# CH32V303VCT6-R0.net
KiCad netlist of a schematic drawn in Altium Designer
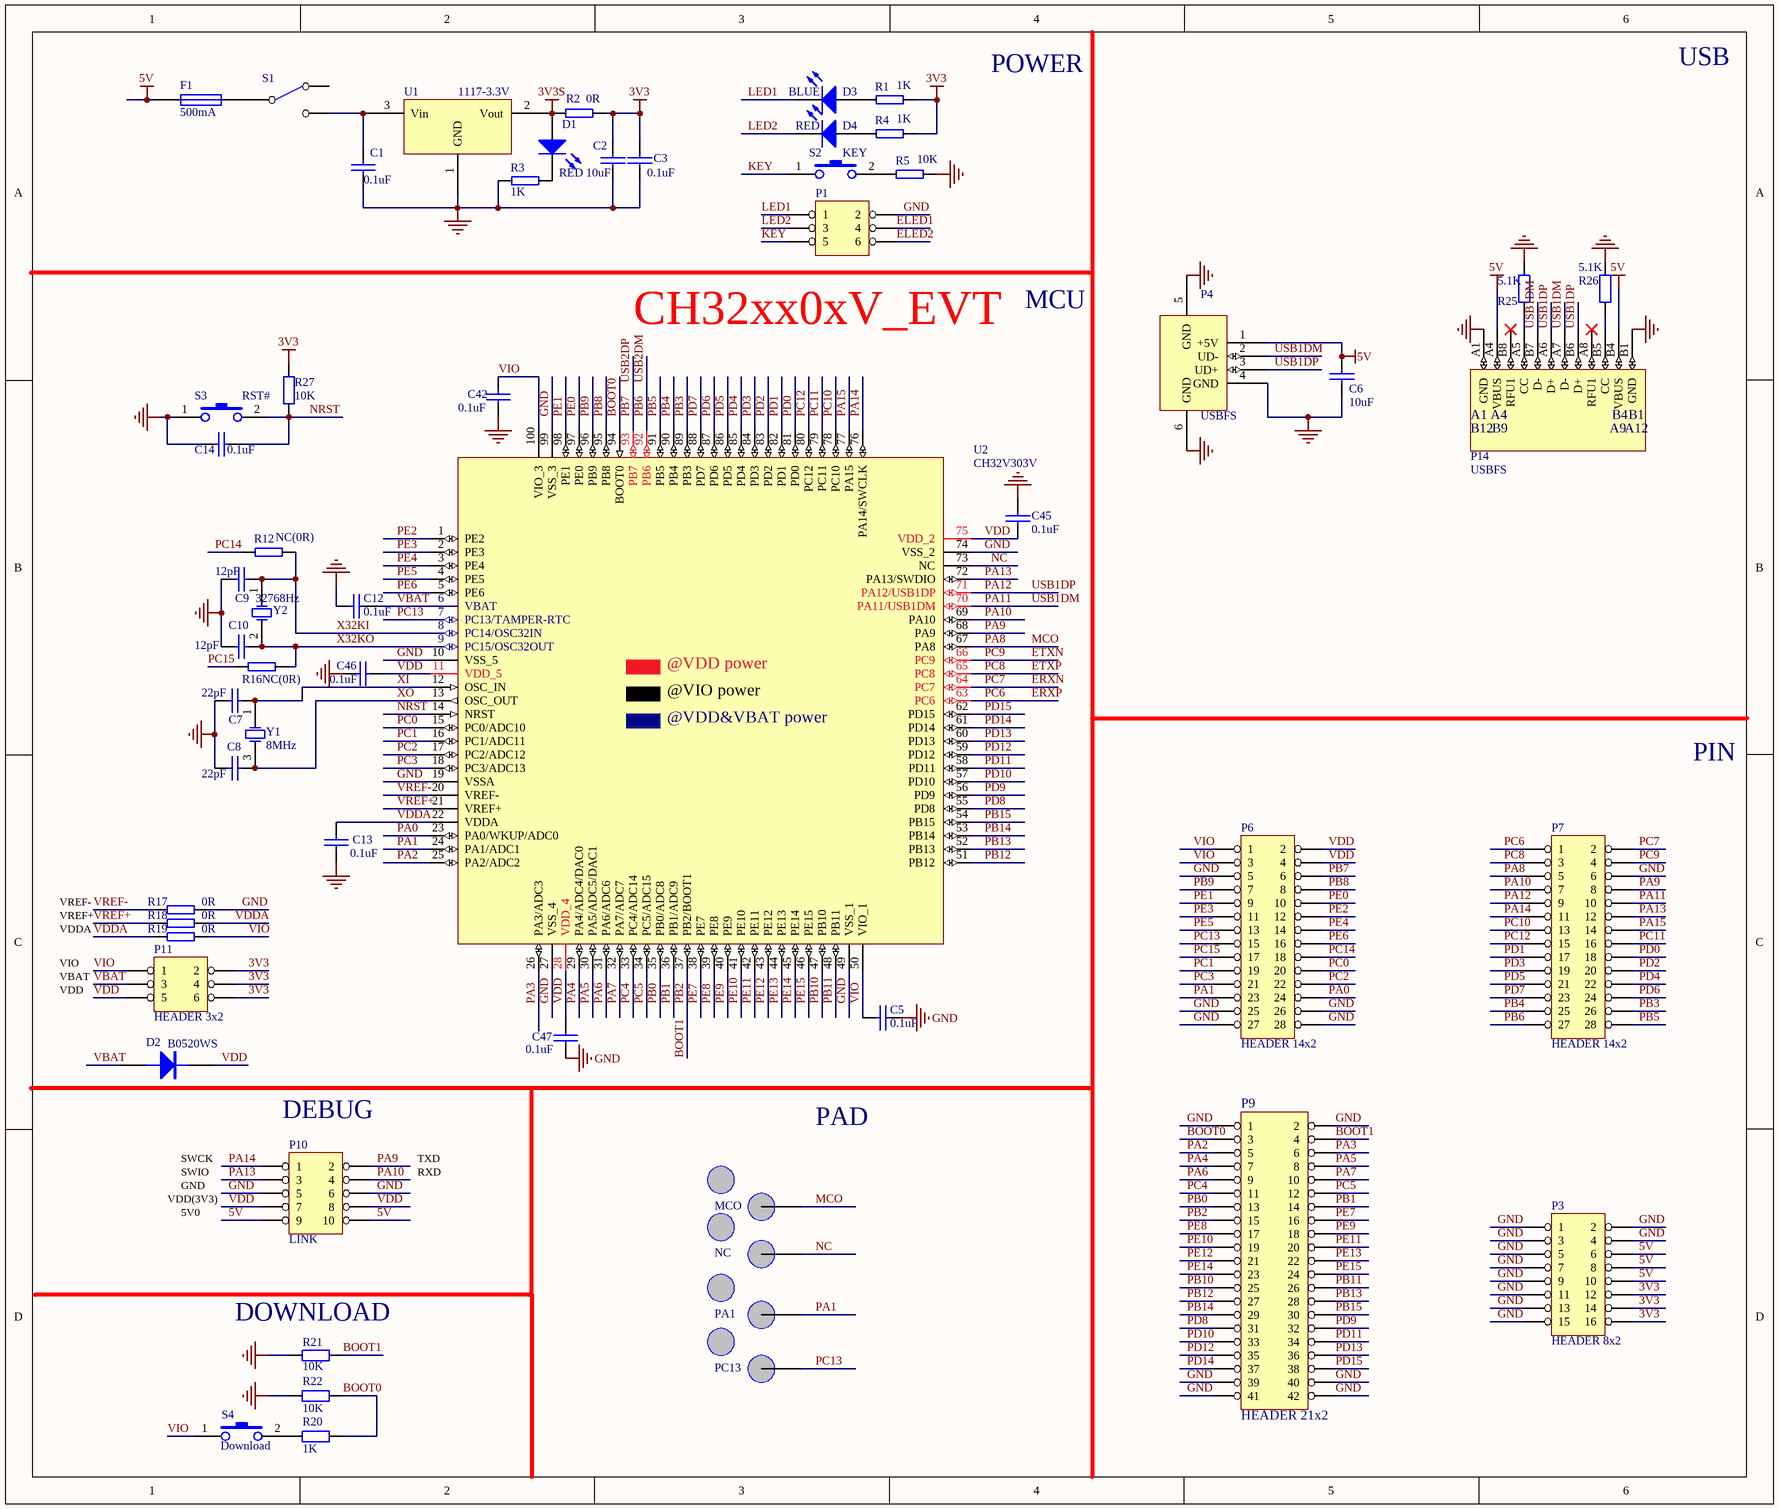
[diagram p0: CH32V303VCT6-R0.SchDoc]

(export (version "E")
  (design (tool "Eeschema 10.0.6"))
  (components
    (comp (ref "C1")
      (value "0.1uF")
      (footprint "0603_C")
      (description "Capacitor")
      (libsource (lib "*") (part "CAP"))
    )
    (comp (ref "C2")
      (value "10uF")
      (footprint "3216_C")
      (description "Capacitor")
      (libsource (lib "*") (part "CAP"))
    )
    (comp (ref "C3")
      (value "0.1uF")
      (footprint "0603_C")
      (description "Capacitor")
      (libsource (lib "*") (part "CAP"))
    )
    (comp (ref "C5")
      (value "0.1uF")
      (footprint "0603_C")
      (description "Capacitor")
      (libsource (lib "*") (part "CAP"))
    )
    (comp (ref "C6")
      (value "10uF")
      (footprint "3216_C")
      (description "Capacitor")
      (libsource (lib "") (part "CAP_1"))
    )
    (comp (ref "C7")
      (value "22pF")
      (footprint "0603_C")
      (description "Capacitor")
      (libsource (lib "*") (part "CAP"))
    )
    (comp (ref "C8")
      (value "22pF")
      (footprint "0603_C")
      (description "Capacitor")
      (libsource (lib "*") (part "CAP"))
    )
    (comp (ref "C9")
      (value "12pF")
      (footprint "0603_C")
      (description "Capacitor")
      (libsource (lib "*") (part "CAP"))
    )
    (comp (ref "C10")
      (value "12pF")
      (footprint "0603_C")
      (description "Capacitor")
      (libsource (lib "*") (part "CAP"))
    )
    (comp (ref "C12")
      (value "0.1uF")
      (footprint "0603_C")
      (description "Capacitor")
      (libsource (lib "*") (part "CAP"))
    )
    (comp (ref "C13")
      (value "0.1uF")
      (footprint "0603_C")
      (description "Capacitor")
      (libsource (lib "*") (part "CAP"))
    )
    (comp (ref "C14")
      (value "0.1uF")
      (footprint "0603_C")
      (description "Capacitor")
      (libsource (lib "") (part "CAP_1"))
    )
    (comp (ref "C42")
      (value "0.1uF")
      (footprint "0603_C")
      (description "Capacitor")
      (libsource (lib "*") (part "CAP"))
    )
    (comp (ref "C45")
      (value "0.1uF")
      (footprint "0603_C")
      (description "Capacitor")
      (libsource (lib "*") (part "CAP"))
    )
    (comp (ref "C46")
      (value "0.1uF")
      (footprint "0603_C")
      (description "Capacitor")
      (libsource (lib "*") (part "CAP"))
    )
    (comp (ref "C47")
      (value "0.1uF")
      (footprint "0603_C")
      (description "Capacitor")
      (libsource (lib "*") (part "CAP"))
    )
    (comp (ref "D1")
      (value "RED")
      (footprint "0603+")
      (description "Typical INFRARED GaAs LED")
      (fields (field (name "PUBLISHER") "Altium Limited"))
      (libsource (lib "*") (part "LED0"))
    )
    (comp (ref "D2")
      (value "B0520WS")
      (footprint "SOD-323")
      (description "Diode")
      (libsource (lib "*") (part "DIODE"))
    )
    (comp (ref "D3")
      (value "BLUE")
      (footprint "0603+")
      (description "Typical INFRARED GaAs LED")
      (fields (field (name "PUBLISHER") "Altium Limited"))
      (libsource (lib "*") (part "LED0"))
    )
    (comp (ref "D4")
      (value "RED")
      (footprint "0603+")
      (description "Typical INFRARED GaAs LED")
      (fields (field (name "PUBLISHER") "Altium Limited"))
      (libsource (lib "*") (part "LED0"))
    )
    (comp (ref "F1")
      (value "500mA")
      (footprint "0805")
      (description "Fuse")
      (libsource (lib "wch_sch_others") (part "FUSE1"))
    )
    (comp (ref "MCO")
      (value "Testpoint")
      (footprint "TESTPOINT1")
      (description "测试点")
      (libsource (lib "wch_sch_others") (part "Testpoint"))
    )
    (comp (ref "NC")
      (value "Testpoint")
      (footprint "TESTPOINT1")
      (description "测试点")
      (libsource (lib "wch_sch_others") (part "Testpoint"))
    )
    (comp (ref "P1")
      (value "IO")
      (footprint "MYPCB:IDC6-2.54mm")
      (description "Header, 3-Pin, Dual row")
      (libsource (lib "wch_sch_others") (part "HEADER 3x2"))
    )
    (comp (ref "P3")
      (value "HEADER 8x2")
      (footprint "MYPCB:IDC16-2.54mm")
      (description "Header, 8-Pin, Dual row")
      (libsource (lib "wch_sch_others") (part "HEADER 8x2"))
    )
    (comp (ref "P4")
      (value "USBFS")
      (footprint "USBAF")
      (description "USB Port")
      (libsource (lib "*") (part "USB"))
    )
    (comp (ref "P6")
      (value "HEADER 14x2")
      (footprint "MYPCB:IDC28-2.54MM")
      (description "Header, 14-Pin, Dual row")
      (libsource (lib "wch_sch_others") (part "HEADER 14x2"))
    )
    (comp (ref "P7")
      (value "HEADER 14x2")
      (footprint "MYPCB:IDC28-2.54MM")
      (description "Header, 14-Pin, Dual row")
      (libsource (lib "wch_sch_others") (part "HEADER 14x2"))
    )
    (comp (ref "P9")
      (value "HEADER 21x2")
      (footprint "MYPCB:IDC42-2.54MM")
      (description "Header, 21-Pin, Dual row")
      (libsource (lib "wch_sch_others") (part "HEADER 21x2"))
    )
    (comp (ref "P10")
      (value "LINK")
      (footprint "MYPCB:IDC10-2.54mm")
      (description "Header, 5-Pin, Dual row")
      (libsource (lib "wch_sch_others") (part "HEADER 5x2"))
    )
    (comp (ref "P11")
      (value "HEADER 3x2")
      (footprint "MYPCB:IDC6-2.54mm")
      (description "Header, 3-Pin, Dual row")
      (libsource (lib "wch_sch_others") (part "HEADER 3x2"))
    )
    (comp (ref "P14")
      (value "USBFS")
      (footprint "TYPE-C-Receptacle-2.0")
      (libsource (lib "*") (part "TYPE-C1"))
    )
    (comp (ref "PA1")
      (value "Testpoint")
      (footprint "TESTPOINT1")
      (description "测试点")
      (libsource (lib "wch_sch_others") (part "Testpoint"))
    )
    (comp (ref "PC13")
      (value "Testpoint")
      (footprint "TESTPOINT1")
      (description "测试点")
      (libsource (lib "wch_sch_others") (part "Testpoint"))
    )
    (comp (ref "R1") (value "1K") (footprint "0603") (libsource (lib "wch_sch_others") (part "RES")))
    (comp (ref "R2") (value "0R") (footprint "0603") (libsource (lib "wch_sch_others") (part "RES")))
    (comp (ref "R3") (value "1K") (footprint "0603") (libsource (lib "wch_sch_others") (part "RES")))
    (comp (ref "R4") (value "1K") (footprint "0603") (libsource (lib "wch_sch_others") (part "RES")))
    (comp (ref "R5") (value "10K") (footprint "0603") (libsource (lib "wch_sch_others") (part "RES")))
    (comp (ref "R12") (value "NC(0R)") (footprint "0603") (libsource (lib "wch_sch_others") (part "RES")))
    (comp (ref "R16") (value "NC(0R)") (footprint "0603") (libsource (lib "wch_sch_others") (part "RES")))
    (comp (ref "R17") (value "0R") (footprint "0603") (libsource (lib "*") (part "R")))
    (comp (ref "R18") (value "0R") (footprint "0603") (libsource (lib "*") (part "R")))
    (comp (ref "R19") (value "0R") (footprint "0603") (libsource (lib "*") (part "R")))
    (comp (ref "R20")
      (value "1K")
      (footprint "0603")
      (description "Resistor")
      (fields (field (name "PUBLISHER") "Altium Limited"))
      (libsource (lib "Miscellaneous Devices") (part "Res2"))
    )
    (comp (ref "R21")
      (value "10K")
      (footprint "0603")
      (description "Resistor")
      (fields (field (name "PUBLISHER") "Altium Limited"))
      (libsource (lib "Miscellaneous Devices") (part "Res2"))
    )
    (comp (ref "R22")
      (value "10K")
      (footprint "0603")
      (description "Resistor")
      (fields (field (name "PUBLISHER") "Altium Limited"))
      (libsource (lib "Miscellaneous Devices") (part "Res2"))
    )
    (comp (ref "R25")
      (value "5.1K")
      (footprint "0603")
      (description "Resistor")
      (libsource (lib "") (part "Res2_1"))
    )
    (comp (ref "R26")
      (value "5.1K")
      (footprint "0603")
      (description "Resistor")
      (libsource (lib "") (part "Res2_1"))
    )
    (comp (ref "R27")
      (value "10K")
      (footprint "0603")
      (description "Resistor")
      (fields (field (name "PUBLISHER") "Altium Limited"))
      (libsource (lib "") (part "Res2_1"))
    )
    (comp (ref "S1") (value "SW SPDT") (footprint "KEY2") (libsource (lib "*") (part "SW SPDT")))
    (comp (ref "S2")
      (value "KEY")
      (footprint "SMD_6.1x3.65x2.5mm-KEY")
      (libsource (lib "wch_sch_others") (part "KEY1"))
    )
    (comp (ref "S3")
      (value "RST#")
      (footprint "SMD_6.1x3.65x2.5mm-KEY")
      (libsource (lib "wch_sch_others") (part "KEY1"))
    )
    (comp (ref "S4")
      (value "Download")
      (footprint "SMD_6.1x3.65x2.5mm-KEY")
      (libsource (lib "wch_sch_others") (part "KEY1"))
    )
    (comp (ref "U1")
      (value "1117-3.3V")
      (footprint "SOT-223")
      (libsource (lib "wch_sch_others") (part "1117-3.3V"))
    )
    (comp (ref "U2")
      (value "CH32V303V")
      (footprint "LQFP100")
      (description "RISC-V FPU HD-MCU, 144MHz, 8*UART, 10*Timer, 4*OPA")
      (libsource (lib "CHXXX") (part "CH32V303V"))
    )
    (comp (ref "Y1")
      (value "8MHz")
      (footprint "XT3225")
      (description "Crystal Oscillator")
      (fields (field (name "PUBLISHER") "Altium Limited"))
      (libsource (lib "*") (part "XTAL"))
    )
    (comp (ref "Y2")
      (value "32768Hz")
      (footprint "FC-135")
      (description "Crystal Oscillator")
      (fields (field (name "PUBLISHER") "Altium Limited"))
      (libsource (lib "") (part "XTAL_1"))
    )
  )
  (nets
    (net (code "2") (name "/BOOT0") (class "Default")
      (node (ref "P9") (pin "3") (pinfunction "3_3") (pintype "passive"))
      (node (ref "R20") (pin "1") (pinfunction "1_1") (pintype "passive"))
      (node (ref "R22") (pin "1") (pinfunction "1_1") (pintype "passive"))
      (node (ref "U2") (pin "94") (pinfunction "BOOT0_94") (pintype "input"))
    )
    (net (code "3") (name "/BOOT1") (class "Default")
      (node (ref "P9") (pin "15") (pinfunction "15_15") (pintype "passive"))
      (node (ref "P9") (pin "4") (pinfunction "4_4") (pintype "passive"))
      (node (ref "R21") (pin "1") (pinfunction "1_1") (pintype "passive"))
      (node (ref "U2") (pin "37") (pinfunction "PB2/BOOT1_37") (pintype "bidirectional"))
    )
    (net (code "4") (name "/ELED1") (class "Default")
      (node (ref "P1") (pin "4") (pinfunction "4_4") (pintype "passive"))
    )
    (net (code "5") (name "/ELED2") (class "Default")
      (node (ref "P1") (pin "6") (pinfunction "6_6") (pintype "passive"))
    )
    (net (code "6") (name "/ERXN") (class "Default")
      (node (ref "P7") (pin "2") (pinfunction "2_2") (pintype "passive"))
      (node (ref "U2") (pin "64") (pinfunction "PC7_64") (pintype "bidirectional"))
    )
    (net (code "7") (name "/ERXP") (class "Default")
      (node (ref "P7") (pin "1") (pinfunction "1_1") (pintype "passive"))
      (node (ref "U2") (pin "63") (pinfunction "PC6_63") (pintype "bidirectional"))
    )
    (net (code "8") (name "/ETXN") (class "Default")
      (node (ref "P7") (pin "4") (pinfunction "4_4") (pintype "passive"))
      (node (ref "U2") (pin "66") (pinfunction "PC9_66") (pintype "bidirectional"))
    )
    (net (code "9") (name "/ETXP") (class "Default")
      (node (ref "P7") (pin "3") (pinfunction "3_3") (pintype "passive"))
      (node (ref "U2") (pin "65") (pinfunction "PC8_65") (pintype "bidirectional"))
    )
    (net (code "10") (name "/KEY") (class "Default")
      (node (ref "P1") (pin "5") (pinfunction "5_5") (pintype "passive"))
      (node (ref "S2") (pin "1") (pinfunction "1_1") (pintype "passive"))
    )
    (net (code "11") (name "/LED1") (class "Default")
      (node (ref "D3") (pin "2") (pinfunction "K_2") (pintype "passive"))
      (node (ref "P1") (pin "1") (pinfunction "1_1") (pintype "passive"))
    )
    (net (code "12") (name "/LED2") (class "Default")
      (node (ref "D4") (pin "2") (pinfunction "K_2") (pintype "passive"))
      (node (ref "P1") (pin "3") (pinfunction "3_3") (pintype "passive"))
    )
    (net (code "13") (name "/MCO") (class "Default")
      (node (ref "MCO") (pin "1") (pinfunction "point_1") (pintype "passive"))
      (node (ref "P7") (pin "5") (pinfunction "5_5") (pintype "passive"))
      (node (ref "U2") (pin "67") (pinfunction "PA8_67") (pintype "bidirectional"))
    )
    (net (code "14") (name "/NC") (class "Default")
      (node (ref "NC") (pin "1") (pinfunction "point_1") (pintype "passive"))
      (node (ref "U2") (pin "73") (pinfunction "NC_73") (pintype "tri_state"))
    )
    (net (code "15") (name "/NRST") (class "Default")
      (node (ref "C14") (pin "2") (pinfunction "2_2") (pintype "passive"))
      (node (ref "R27") (pin "1") (pinfunction "1_1") (pintype "passive"))
      (node (ref "S3") (pin "2") (pinfunction "2_2") (pintype "passive"))
      (node (ref "U2") (pin "14") (pinfunction "NRST_14") (pintype "input"))
    )
    (net (code "16") (name "/PA0") (class "Default")
      (node (ref "P6") (pin "24") (pinfunction "24_24") (pintype "passive"))
      (node (ref "U2") (pin "23") (pinfunction "PA0/WKUP/ADC0_23") (pintype "bidirectional"))
    )
    (net (code "17") (name "/PA1") (class "Default")
      (node (ref "P6") (pin "23") (pinfunction "23_23") (pintype "passive"))
      (node (ref "PA1") (pin "1") (pinfunction "point_1") (pintype "passive"))
      (node (ref "U2") (pin "24") (pinfunction "PA1/ADC1_24") (pintype "bidirectional"))
    )
    (net (code "18") (name "/PA2") (class "Default")
      (node (ref "P9") (pin "5") (pinfunction "5_5") (pintype "passive"))
      (node (ref "U2") (pin "25") (pinfunction "PA2/ADC2_25") (pintype "bidirectional"))
    )
    (net (code "19") (name "/PA3") (class "Default")
      (node (ref "P9") (pin "6") (pinfunction "6_6") (pintype "passive"))
      (node (ref "U2") (pin "26") (pinfunction "PA3/ADC3_26") (pintype "bidirectional"))
    )
    (net (code "20") (name "/PA4") (class "Default")
      (node (ref "P9") (pin "7") (pinfunction "7_7") (pintype "passive"))
      (node (ref "U2") (pin "29") (pinfunction "PA4/ADC4/DAC0_29") (pintype "bidirectional"))
    )
    (net (code "21") (name "/PA5") (class "Default")
      (node (ref "P9") (pin "8") (pinfunction "8_8") (pintype "passive"))
      (node (ref "U2") (pin "30") (pinfunction "PA5/ADC5/DAC1_30") (pintype "bidirectional"))
    )
    (net (code "22") (name "/PA6") (class "Default")
      (node (ref "P9") (pin "9") (pinfunction "9_9") (pintype "passive"))
      (node (ref "U2") (pin "31") (pinfunction "PA6/ADC6_31") (pintype "bidirectional"))
    )
    (net (code "23") (name "/PA7") (class "Default")
      (node (ref "P9") (pin "10") (pinfunction "10_10") (pintype "passive"))
      (node (ref "U2") (pin "32") (pinfunction "PA7/ADC7_32") (pintype "bidirectional"))
    )
    (net (code "24") (name "/PA9") (class "Default")
      (node (ref "P10") (pin "2") (pinfunction "2_2") (pintype "passive"))
      (node (ref "P7") (pin "8") (pinfunction "8_8") (pintype "passive"))
      (node (ref "U2") (pin "68") (pinfunction "PA9_68") (pintype "bidirectional"))
    )
    (net (code "25") (name "/PA10") (class "Default")
      (node (ref "P10") (pin "4") (pinfunction "4_4") (pintype "passive"))
      (node (ref "P7") (pin "7") (pinfunction "7_7") (pintype "passive"))
      (node (ref "U2") (pin "69") (pinfunction "PA10_69") (pintype "bidirectional"))
    )
    (net (code "26") (name "/PA11") (class "Default")
      (node (ref "P14") (pin "A7") (pinfunction "D-_A7") (pintype "bidirectional"))
      (node (ref "P14") (pin "B7") (pinfunction "D-_B7") (pintype "bidirectional"))
      (node (ref "P4") (pin "2") (pinfunction "UD-_2") (pintype "bidirectional"))
      (node (ref "P7") (pin "10") (pinfunction "10_10") (pintype "passive"))
      (node (ref "U2") (pin "70") (pinfunction "PA11/USB1DM_70") (pintype "bidirectional"))
    )
    (net (code "27") (name "/PA12") (class "Default")
      (node (ref "P14") (pin "A6") (pinfunction "D+_A6") (pintype "bidirectional"))
      (node (ref "P14") (pin "B6") (pinfunction "D+_B6") (pintype "bidirectional"))
      (node (ref "P4") (pin "3") (pinfunction "UD+_3") (pintype "bidirectional"))
      (node (ref "P7") (pin "9") (pinfunction "9_9") (pintype "passive"))
      (node (ref "U2") (pin "71") (pinfunction "PA12/USB1DP_71") (pintype "bidirectional"))
    )
    (net (code "28") (name "/PA13") (class "Default")
      (node (ref "P10") (pin "3") (pinfunction "3_3") (pintype "passive"))
      (node (ref "P7") (pin "12") (pinfunction "12_12") (pintype "passive"))
      (node (ref "U2") (pin "72") (pinfunction "PA13/SWDIO_72") (pintype "bidirectional"))
    )
    (net (code "29") (name "/PA14") (class "Default")
      (node (ref "P10") (pin "1") (pinfunction "1_1") (pintype "passive"))
      (node (ref "P7") (pin "11") (pinfunction "11_11") (pintype "passive"))
      (node (ref "U2") (pin "76") (pinfunction "PA14/SWCLK_76") (pintype "bidirectional"))
    )
    (net (code "30") (name "/PA15") (class "Default")
      (node (ref "P7") (pin "14") (pinfunction "14_14") (pintype "passive"))
      (node (ref "U2") (pin "77") (pinfunction "PA15_77") (pintype "bidirectional"))
    )
    (net (code "31") (name "/PB0") (class "Default")
      (node (ref "P9") (pin "13") (pinfunction "13_13") (pintype "passive"))
      (node (ref "U2") (pin "35") (pinfunction "PB0/ADC8_35") (pintype "bidirectional"))
    )
    (net (code "32") (name "/PB1") (class "Default")
      (node (ref "P9") (pin "14") (pinfunction "14_14") (pintype "passive"))
      (node (ref "U2") (pin "36") (pinfunction "PB1/ADC9_36") (pintype "bidirectional"))
    )
    (net (code "33") (name "/PB3") (class "Default")
      (node (ref "P7") (pin "26") (pinfunction "26_26") (pintype "passive"))
      (node (ref "U2") (pin "89") (pinfunction "PB3_89") (pintype "bidirectional"))
    )
    (net (code "34") (name "/PB4") (class "Default")
      (node (ref "P7") (pin "25") (pinfunction "25_25") (pintype "passive"))
      (node (ref "U2") (pin "90") (pinfunction "PB4_90") (pintype "bidirectional"))
    )
    (net (code "35") (name "/PB5") (class "Default")
      (node (ref "P7") (pin "28") (pinfunction "28_28") (pintype "passive"))
      (node (ref "U2") (pin "91") (pinfunction "PB5_91") (pintype "bidirectional"))
    )
    (net (code "36") (name "/PB6") (class "Default")
      (node (ref "P7") (pin "27") (pinfunction "27_27") (pintype "passive"))
      (node (ref "U2") (pin "92") (pinfunction "PB6_92") (pintype "bidirectional"))
    )
    (net (code "37") (name "/PB7") (class "Default")
      (node (ref "P6") (pin "6") (pinfunction "6_6") (pintype "passive"))
      (node (ref "U2") (pin "93") (pinfunction "PB7_93") (pintype "bidirectional"))
    )
    (net (code "38") (name "/PB8") (class "Default")
      (node (ref "P6") (pin "8") (pinfunction "8_8") (pintype "passive"))
      (node (ref "U2") (pin "95") (pinfunction "PB8_95") (pintype "bidirectional"))
    )
    (net (code "39") (name "/PB9") (class "Default")
      (node (ref "P6") (pin "7") (pinfunction "7_7") (pintype "passive"))
      (node (ref "U2") (pin "96") (pinfunction "PB9_96") (pintype "bidirectional"))
    )
    (net (code "40") (name "/PB10") (class "Default")
      (node (ref "P9") (pin "25") (pinfunction "25_25") (pintype "passive"))
      (node (ref "U2") (pin "47") (pinfunction "PB10_47") (pintype "bidirectional"))
    )
    (net (code "41") (name "/PB11") (class "Default")
      (node (ref "P9") (pin "26") (pinfunction "26_26") (pintype "passive"))
      (node (ref "U2") (pin "48") (pinfunction "PB11_48") (pintype "bidirectional"))
    )
    (net (code "42") (name "/PB12") (class "Default")
      (node (ref "P9") (pin "27") (pinfunction "27_27") (pintype "passive"))
      (node (ref "U2") (pin "51") (pinfunction "PB12_51") (pintype "bidirectional"))
    )
    (net (code "43") (name "/PB13") (class "Default")
      (node (ref "P9") (pin "28") (pinfunction "28_28") (pintype "passive"))
      (node (ref "U2") (pin "52") (pinfunction "PB13_52") (pintype "bidirectional"))
    )
    (net (code "44") (name "/PB14") (class "Default")
      (node (ref "P9") (pin "29") (pinfunction "29_29") (pintype "passive"))
      (node (ref "U2") (pin "53") (pinfunction "PB14_53") (pintype "bidirectional"))
    )
    (net (code "45") (name "/PB15") (class "Default")
      (node (ref "P9") (pin "30") (pinfunction "30_30") (pintype "passive"))
      (node (ref "U2") (pin "54") (pinfunction "PB15_54") (pintype "bidirectional"))
    )
    (net (code "46") (name "/PC0") (class "Default")
      (node (ref "P6") (pin "20") (pinfunction "20_20") (pintype "passive"))
      (node (ref "U2") (pin "15") (pinfunction "PC0/ADC10_15") (pintype "bidirectional"))
    )
    (net (code "47") (name "/PC1") (class "Default")
      (node (ref "P6") (pin "19") (pinfunction "19_19") (pintype "passive"))
      (node (ref "U2") (pin "16") (pinfunction "PC1/ADC11_16") (pintype "bidirectional"))
    )
    (net (code "48") (name "/PC2") (class "Default")
      (node (ref "P6") (pin "22") (pinfunction "22_22") (pintype "passive"))
      (node (ref "U2") (pin "17") (pinfunction "PC2/ADC12_17") (pintype "bidirectional"))
    )
    (net (code "49") (name "/PC3") (class "Default")
      (node (ref "P6") (pin "21") (pinfunction "21_21") (pintype "passive"))
      (node (ref "U2") (pin "18") (pinfunction "PC3/ADC13_18") (pintype "bidirectional"))
    )
    (net (code "50") (name "/PC4") (class "Default")
      (node (ref "P9") (pin "11") (pinfunction "11_11") (pintype "passive"))
      (node (ref "U2") (pin "33") (pinfunction "PC4/ADC14_33") (pintype "bidirectional"))
    )
    (net (code "51") (name "/PC5") (class "Default")
      (node (ref "P9") (pin "12") (pinfunction "12_12") (pintype "passive"))
      (node (ref "U2") (pin "34") (pinfunction "PC5/ADC15_34") (pintype "bidirectional"))
    )
    (net (code "52") (name "/PC10") (class "Default")
      (node (ref "P7") (pin "13") (pinfunction "13_13") (pintype "passive"))
      (node (ref "U2") (pin "78") (pinfunction "PC10_78") (pintype "bidirectional"))
    )
    (net (code "53") (name "/PC11") (class "Default")
      (node (ref "P7") (pin "16") (pinfunction "16_16") (pintype "passive"))
      (node (ref "U2") (pin "79") (pinfunction "PC11_79") (pintype "bidirectional"))
    )
    (net (code "54") (name "/PC12") (class "Default")
      (node (ref "P7") (pin "15") (pinfunction "15_15") (pintype "passive"))
      (node (ref "U2") (pin "80") (pinfunction "PC12_80") (pintype "bidirectional"))
    )
    (net (code "55") (name "/PC13") (class "Default")
      (node (ref "P6") (pin "15") (pinfunction "15_15") (pintype "passive"))
      (node (ref "PC13") (pin "1") (pinfunction "point_1") (pintype "passive"))
      (node (ref "U2") (pin "7") (pinfunction "PC13/TAMPER-RTC_7") (pintype "bidirectional"))
    )
    (net (code "56") (name "/PC14") (class "Default")
      (node (ref "P6") (pin "18") (pinfunction "18_18") (pintype "passive"))
      (node (ref "R12") (pin "1") (pintype "passive"))
    )
    (net (code "57") (name "/PC15") (class "Default")
      (node (ref "P6") (pin "17") (pinfunction "17_17") (pintype "passive"))
      (node (ref "R16") (pin "1") (pintype "passive"))
    )
    (net (code "58") (name "/PD0") (class "Default")
      (node (ref "P7") (pin "18") (pinfunction "18_18") (pintype "passive"))
      (node (ref "U2") (pin "81") (pinfunction "PD0_81") (pintype "bidirectional"))
    )
    (net (code "59") (name "/PD1") (class "Default")
      (node (ref "P7") (pin "17") (pinfunction "17_17") (pintype "passive"))
      (node (ref "U2") (pin "82") (pinfunction "PD1_82") (pintype "bidirectional"))
    )
    (net (code "60") (name "/PD2") (class "Default")
      (node (ref "P7") (pin "20") (pinfunction "20_20") (pintype "passive"))
      (node (ref "U2") (pin "83") (pinfunction "PD2_83") (pintype "bidirectional"))
    )
    (net (code "61") (name "/PD3") (class "Default")
      (node (ref "P7") (pin "19") (pinfunction "19_19") (pintype "passive"))
      (node (ref "U2") (pin "84") (pinfunction "PD3_84") (pintype "bidirectional"))
    )
    (net (code "62") (name "/PD4") (class "Default")
      (node (ref "P7") (pin "22") (pinfunction "22_22") (pintype "passive"))
      (node (ref "U2") (pin "85") (pinfunction "PD4_85") (pintype "bidirectional"))
    )
    (net (code "63") (name "/PD5") (class "Default")
      (node (ref "P7") (pin "21") (pinfunction "21_21") (pintype "passive"))
      (node (ref "U2") (pin "86") (pinfunction "PD5_86") (pintype "bidirectional"))
    )
    (net (code "64") (name "/PD6") (class "Default")
      (node (ref "P7") (pin "24") (pinfunction "24_24") (pintype "passive"))
      (node (ref "U2") (pin "87") (pinfunction "PD6_87") (pintype "bidirectional"))
    )
    (net (code "65") (name "/PD7") (class "Default")
      (node (ref "P7") (pin "23") (pinfunction "23_23") (pintype "passive"))
      (node (ref "U2") (pin "88") (pinfunction "PD7_88") (pintype "bidirectional"))
    )
    (net (code "66") (name "/PD8") (class "Default")
      (node (ref "P9") (pin "31") (pinfunction "31_31") (pintype "passive"))
      (node (ref "U2") (pin "55") (pinfunction "PD8_55") (pintype "bidirectional"))
    )
    (net (code "67") (name "/PD9") (class "Default")
      (node (ref "P9") (pin "32") (pinfunction "32_32") (pintype "passive"))
      (node (ref "U2") (pin "56") (pinfunction "PD9_56") (pintype "bidirectional"))
    )
    (net (code "68") (name "/PD10") (class "Default")
      (node (ref "P9") (pin "33") (pinfunction "33_33") (pintype "passive"))
      (node (ref "U2") (pin "57") (pinfunction "PD10_57") (pintype "bidirectional"))
    )
    (net (code "69") (name "/PD11") (class "Default")
      (node (ref "P9") (pin "34") (pinfunction "34_34") (pintype "passive"))
      (node (ref "U2") (pin "58") (pinfunction "PD11_58") (pintype "bidirectional"))
    )
    (net (code "70") (name "/PD12") (class "Default")
      (node (ref "P9") (pin "35") (pinfunction "35_35") (pintype "passive"))
      (node (ref "U2") (pin "59") (pinfunction "PD12_59") (pintype "bidirectional"))
    )
    (net (code "71") (name "/PD13") (class "Default")
      (node (ref "P9") (pin "36") (pinfunction "36_36") (pintype "passive"))
      (node (ref "U2") (pin "60") (pinfunction "PD13_60") (pintype "bidirectional"))
    )
    (net (code "72") (name "/PD14") (class "Default")
      (node (ref "P9") (pin "37") (pinfunction "37_37") (pintype "passive"))
      (node (ref "U2") (pin "61") (pinfunction "PD14_61") (pintype "bidirectional"))
    )
    (net (code "73") (name "/PD15") (class "Default")
      (node (ref "P9") (pin "38") (pinfunction "38_38") (pintype "passive"))
      (node (ref "U2") (pin "62") (pinfunction "PD15_62") (pintype "bidirectional"))
    )
    (net (code "74") (name "/PE0") (class "Default")
      (node (ref "P6") (pin "10") (pinfunction "10_10") (pintype "passive"))
      (node (ref "U2") (pin "97") (pinfunction "PE0_97") (pintype "bidirectional"))
    )
    (net (code "75") (name "/PE1") (class "Default")
      (node (ref "P6") (pin "9") (pinfunction "9_9") (pintype "passive"))
      (node (ref "U2") (pin "98") (pinfunction "PE1_98") (pintype "bidirectional"))
    )
    (net (code "76") (name "/PE2") (class "Default")
      (node (ref "P6") (pin "12") (pinfunction "12_12") (pintype "passive"))
      (node (ref "U2") (pin "1") (pinfunction "PE2_1") (pintype "bidirectional"))
    )
    (net (code "77") (name "/PE3") (class "Default")
      (node (ref "P6") (pin "11") (pinfunction "11_11") (pintype "passive"))
      (node (ref "U2") (pin "2") (pinfunction "PE3_2") (pintype "bidirectional"))
    )
    (net (code "78") (name "/PE4") (class "Default")
      (node (ref "P6") (pin "14") (pinfunction "14_14") (pintype "passive"))
      (node (ref "U2") (pin "3") (pinfunction "PE4_3") (pintype "bidirectional"))
    )
    (net (code "79") (name "/PE5") (class "Default")
      (node (ref "P6") (pin "13") (pinfunction "13_13") (pintype "passive"))
      (node (ref "U2") (pin "4") (pinfunction "PE5_4") (pintype "bidirectional"))
    )
    (net (code "80") (name "/PE6") (class "Default")
      (node (ref "P6") (pin "16") (pinfunction "16_16") (pintype "passive"))
      (node (ref "U2") (pin "5") (pinfunction "PE6_5") (pintype "bidirectional"))
    )
    (net (code "81") (name "/PE7") (class "Default")
      (node (ref "P9") (pin "16") (pinfunction "16_16") (pintype "passive"))
      (node (ref "U2") (pin "38") (pinfunction "PE7_38") (pintype "bidirectional"))
    )
    (net (code "82") (name "/PE8") (class "Default")
      (node (ref "P9") (pin "17") (pinfunction "17_17") (pintype "passive"))
      (node (ref "U2") (pin "39") (pinfunction "PE8_39") (pintype "bidirectional"))
    )
    (net (code "83") (name "/PE9") (class "Default")
      (node (ref "P9") (pin "18") (pinfunction "18_18") (pintype "passive"))
      (node (ref "U2") (pin "40") (pinfunction "PE9_40") (pintype "bidirectional"))
    )
    (net (code "84") (name "/PE10") (class "Default")
      (node (ref "P9") (pin "19") (pinfunction "19_19") (pintype "passive"))
      (node (ref "U2") (pin "41") (pinfunction "PE10_41") (pintype "bidirectional"))
    )
    (net (code "85") (name "/PE11") (class "Default")
      (node (ref "P9") (pin "20") (pinfunction "20_20") (pintype "passive"))
      (node (ref "U2") (pin "42") (pinfunction "PE11_42") (pintype "bidirectional"))
    )
    (net (code "86") (name "/PE12") (class "Default")
      (node (ref "P9") (pin "21") (pinfunction "21_21") (pintype "passive"))
      (node (ref "U2") (pin "43") (pinfunction "PE12_43") (pintype "bidirectional"))
    )
    (net (code "87") (name "/PE13") (class "Default")
      (node (ref "P9") (pin "22") (pinfunction "22_22") (pintype "passive"))
      (node (ref "U2") (pin "44") (pinfunction "PE13_44") (pintype "bidirectional"))
    )
    (net (code "88") (name "/PE14") (class "Default")
      (node (ref "P9") (pin "23") (pinfunction "23_23") (pintype "passive"))
      (node (ref "U2") (pin "45") (pinfunction "PE14_45") (pintype "bidirectional"))
    )
    (net (code "89") (name "/PE15") (class "Default")
      (node (ref "P9") (pin "24") (pinfunction "24_24") (pintype "passive"))
      (node (ref "U2") (pin "46") (pinfunction "PE15_46") (pintype "bidirectional"))
    )
    (net (code "90") (name "/VBAT") (class "Default")
      (node (ref "C12") (pin "2") (pinfunction "2_2") (pintype "passive"))
      (node (ref "D2") (pin "1") (pinfunction "A_1") (pintype "passive"))
      (node (ref "P11") (pin "3") (pinfunction "3_3") (pintype "passive"))
      (node (ref "U2") (pin "6") (pinfunction "VBAT_6") (pintype "power_in"))
    )
    (net (code "91") (name "/VDD") (class "Default")
      (node (ref "C45") (pin "1") (pinfunction "1_1") (pintype "passive"))
      (node (ref "C46") (pin "1") (pinfunction "1_1") (pintype "passive"))
      (node (ref "C47") (pin "2") (pinfunction "2_2") (pintype "passive"))
      (node (ref "D2") (pin "2") (pinfunction "K_2") (pintype "passive"))
      (node (ref "P10") (pin "7") (pinfunction "7_7") (pintype "passive"))
      (node (ref "P10") (pin "8") (pinfunction "8_8") (pintype "passive"))
      (node (ref "P11") (pin "5") (pinfunction "5_5") (pintype "passive"))
      (node (ref "P6") (pin "2") (pinfunction "2_2") (pintype "passive"))
      (node (ref "P6") (pin "4") (pinfunction "4_4") (pintype "passive"))
      (node (ref "U2") (pin "11") (pinfunction "VDD_5_11") (pintype "power_in"))
      (node (ref "U2") (pin "28") (pinfunction "VDD_4_28") (pintype "power_in"))
      (node (ref "U2") (pin "75") (pinfunction "VDD_2_75") (pintype "power_in"))
    )
    (net (code "92") (name "/VDDA") (class "Default")
      (node (ref "C13") (pin "1") (pinfunction "1_1") (pintype "passive"))
      (node (ref "R18") (pin "1") (pinfunction "1_1") (pintype "passive"))
      (node (ref "R19") (pin "2") (pinfunction "2_2") (pintype "passive"))
      (node (ref "U2") (pin "22") (pinfunction "VDDA_22") (pintype "power_in"))
    )
    (net (code "93") (name "/VIO") (class "Default")
      (node (ref "C42") (pin "2") (pinfunction "2_2") (pintype "passive"))
      (node (ref "C5") (pin "1") (pinfunction "1_1") (pintype "passive"))
      (node (ref "P11") (pin "1") (pinfunction "1_1") (pintype "passive"))
      (node (ref "P6") (pin "1") (pinfunction "1_1") (pintype "passive"))
      (node (ref "P6") (pin "3") (pinfunction "3_3") (pintype "passive"))
      (node (ref "R19") (pin "1") (pinfunction "1_1") (pintype "passive"))
      (node (ref "S4") (pin "1") (pinfunction "1_1") (pintype "passive"))
      (node (ref "U2") (pin "100") (pinfunction "VIO_3_100") (pintype "power_in"))
      (node (ref "U2") (pin "50") (pinfunction "VIO_1_50") (pintype "power_in"))
    )
    (net (code "94") (name "/VREF+") (class "Default")
      (node (ref "R18") (pin "2") (pinfunction "2_2") (pintype "passive"))
      (node (ref "U2") (pin "21") (pinfunction "VREF+_21") (pintype "power_in"))
    )
    (net (code "95") (name "/VREF-") (class "Default")
      (node (ref "R17") (pin "2") (pinfunction "2_2") (pintype "passive"))
      (node (ref "U2") (pin "20") (pinfunction "VREF-_20") (pintype "power_in"))
    )
    (net (code "96") (name "/X32KI") (class "Default")
      (node (ref "C9") (pin "2") (pinfunction "2_2") (pintype "passive"))
      (node (ref "R12") (pin "2") (pintype "passive"))
      (node (ref "U2") (pin "8") (pinfunction "PC14/OSC32IN_8") (pintype "bidirectional"))
      (node (ref "Y2") (pin "1") (pinfunction "OSC1_1") (pintype "passive"))
    )
    (net (code "97") (name "/X32KO") (class "Default")
      (node (ref "C10") (pin "2") (pinfunction "2_2") (pintype "passive"))
      (node (ref "R16") (pin "2") (pintype "passive"))
      (node (ref "U2") (pin "9") (pinfunction "PC15/OSC32OUT_9") (pintype "bidirectional"))
      (node (ref "Y2") (pin "2") (pinfunction "OSC2_2") (pintype "passive"))
    )
    (net (code "98") (name "/XI") (class "Default")
      (node (ref "C7") (pin "2") (pinfunction "2_2") (pintype "passive"))
      (node (ref "U2") (pin "12") (pinfunction "OSC_IN_12") (pintype "input"))
      (node (ref "Y1") (pin "1") (pinfunction "OSC1_1") (pintype "passive"))
    )
    (net (code "99") (name "/XO") (class "Default")
      (node (ref "C8") (pin "2") (pinfunction "2_2") (pintype "passive"))
      (node (ref "U2") (pin "13") (pinfunction "OSC_OUT_13") (pintype "output"))
      (node (ref "Y1") (pin "3") (pinfunction "OSC2_3") (pintype "passive"))
    )
    (net (code "100") (name "3V3") (class "Default")
      (node (ref "C2") (pin "1") (pinfunction "1_1") (pintype "passive"))
      (node (ref "C3") (pin "1") (pinfunction "1_1") (pintype "passive"))
      (node (ref "P11") (pin "2") (pinfunction "2_2") (pintype "passive"))
      (node (ref "P11") (pin "4") (pinfunction "4_4") (pintype "passive"))
      (node (ref "P11") (pin "6") (pinfunction "6_6") (pintype "passive"))
      (node (ref "P3") (pin "12") (pinfunction "12_12") (pintype "passive"))
      (node (ref "P3") (pin "14") (pinfunction "14_14") (pintype "passive"))
      (node (ref "P3") (pin "16") (pinfunction "16_16") (pintype "passive"))
      (node (ref "R1") (pin "1") (pintype "passive"))
      (node (ref "R2") (pin "1") (pintype "passive"))
      (node (ref "R27") (pin "2") (pinfunction "2_2") (pintype "passive"))
      (node (ref "R4") (pin "1") (pintype "passive"))
    )
    (net (code "101") (name "3V3S") (class "Default")
      (node (ref "D1") (pin "1") (pinfunction "A_1") (pintype "passive"))
      (node (ref "R2") (pin "2") (pintype "passive"))
      (node (ref "U1") (pin "2") (pinfunction "Vout_2") (pintype "passive"))
    )
    (net (code "102") (name "5V") (class "Default")
      (node (ref "C6") (pin "1") (pinfunction "1_1") (pintype "passive"))
      (node (ref "F1") (pin "1") (pinfunction "1_1") (pintype "passive"))
      (node (ref "P10") (pin "10") (pinfunction "10_10") (pintype "passive"))
      (node (ref "P10") (pin "9") (pinfunction "9_9") (pintype "passive"))
      (node (ref "P14") (pin "A4") (pinfunction "VBUS_A4") (pintype "bidirectional"))
      (node (ref "P14") (pin "B4") (pinfunction "VBUS_B4") (pintype "bidirectional"))
      (node (ref "P3") (pin "10") (pinfunction "10_10") (pintype "passive"))
      (node (ref "P3") (pin "6") (pinfunction "6_6") (pintype "passive"))
      (node (ref "P3") (pin "8") (pinfunction "8_8") (pintype "passive"))
      (node (ref "P4") (pin "1") (pinfunction "+5V_1") (pintype "power_in"))
    )
    (net (code "103") (name "GND") (class "Default")
      (node (ref "C1") (pin "2") (pinfunction "2_2") (pintype "passive"))
      (node (ref "C10") (pin "1") (pinfunction "1_1") (pintype "passive"))
      (node (ref "C12") (pin "1") (pinfunction "1_1") (pintype "passive"))
      (node (ref "C13") (pin "2") (pinfunction "2_2") (pintype "passive"))
      (node (ref "C14") (pin "1") (pinfunction "1_1") (pintype "passive"))
      (node (ref "C2") (pin "2") (pinfunction "2_2") (pintype "passive"))
      (node (ref "C3") (pin "2") (pinfunction "2_2") (pintype "passive"))
      (node (ref "C42") (pin "1") (pinfunction "1_1") (pintype "passive"))
      (node (ref "C45") (pin "2") (pinfunction "2_2") (pintype "passive"))
      (node (ref "C46") (pin "2") (pinfunction "2_2") (pintype "passive"))
      (node (ref "C47") (pin "1") (pinfunction "1_1") (pintype "passive"))
      (node (ref "C5") (pin "2") (pinfunction "2_2") (pintype "passive"))
      (node (ref "C6") (pin "2") (pinfunction "2_2") (pintype "passive"))
      (node (ref "C7") (pin "1") (pinfunction "1_1") (pintype "passive"))
      (node (ref "C8") (pin "1") (pinfunction "1_1") (pintype "passive"))
      (node (ref "C9") (pin "1") (pinfunction "1_1") (pintype "passive"))
      (node (ref "P1") (pin "2") (pinfunction "2_2") (pintype "passive"))
      (node (ref "P10") (pin "5") (pinfunction "5_5") (pintype "passive"))
      (node (ref "P10") (pin "6") (pinfunction "6_6") (pintype "passive"))
      (node (ref "P14") (pin "A1") (pinfunction "GND_A1") (pintype "bidirectional"))
      (node (ref "P14") (pin "B1") (pinfunction "GND_B1") (pintype "bidirectional"))
      (node (ref "P3") (pin "1") (pinfunction "1_1") (pintype "passive"))
      (node (ref "P3") (pin "11") (pinfunction "11_11") (pintype "passive"))
      (node (ref "P3") (pin "13") (pinfunction "13_13") (pintype "passive"))
      (node (ref "P3") (pin "15") (pinfunction "15_15") (pintype "passive"))
      (node (ref "P3") (pin "2") (pinfunction "2_2") (pintype "passive"))
      (node (ref "P3") (pin "3") (pinfunction "3_3") (pintype "passive"))
      (node (ref "P3") (pin "4") (pinfunction "4_4") (pintype "passive"))
      (node (ref "P3") (pin "5") (pinfunction "5_5") (pintype "passive"))
      (node (ref "P3") (pin "7") (pinfunction "7_7") (pintype "passive"))
      (node (ref "P3") (pin "9") (pinfunction "9_9") (pintype "passive"))
      (node (ref "P4") (pin "4") (pinfunction "GND_4") (pintype "power_in"))
      (node (ref "P4") (pin "5") (pinfunction "GND_5") (pintype "power_in"))
      (node (ref "P4") (pin "6") (pinfunction "GND_6") (pintype "power_in"))
      (node (ref "P6") (pin "25") (pinfunction "25_25") (pintype "passive"))
      (node (ref "P6") (pin "26") (pinfunction "26_26") (pintype "passive"))
      (node (ref "P6") (pin "27") (pinfunction "27_27") (pintype "passive"))
      (node (ref "P6") (pin "28") (pinfunction "28_28") (pintype "passive"))
      (node (ref "P6") (pin "5") (pinfunction "5_5") (pintype "passive"))
      (node (ref "P7") (pin "6") (pinfunction "6_6") (pintype "passive"))
      (node (ref "P9") (pin "1") (pinfunction "1_1") (pintype "passive"))
      (node (ref "P9") (pin "2") (pinfunction "2_2") (pintype "passive"))
      (node (ref "P9") (pin "39") (pinfunction "39_39") (pintype "passive"))
      (node (ref "P9") (pin "40") (pinfunction "40_40") (pintype "passive"))
      (node (ref "P9") (pin "41") (pinfunction "41_41") (pintype "passive"))
      (node (ref "P9") (pin "42") (pinfunction "42_42") (pintype "passive"))
      (node (ref "R17") (pin "1") (pinfunction "1_1") (pintype "passive"))
      (node (ref "R21") (pin "2") (pinfunction "2_2") (pintype "passive"))
      (node (ref "R22") (pin "2") (pinfunction "2_2") (pintype "passive"))
      (node (ref "R25") (pin "2") (pinfunction "2_2") (pintype "passive"))
      (node (ref "R26") (pin "2") (pinfunction "2_2") (pintype "passive"))
      (node (ref "R3") (pin "2") (pintype "passive"))
      (node (ref "R5") (pin "1") (pintype "passive"))
      (node (ref "S3") (pin "1") (pinfunction "1_1") (pintype "passive"))
      (node (ref "U1") (pin "1") (pinfunction "GND_1") (pintype "passive"))
      (node (ref "U2") (pin "10") (pinfunction "VSS_5_10") (pintype "power_in"))
      (node (ref "U2") (pin "19") (pinfunction "VSSA_19") (pintype "power_in"))
      (node (ref "U2") (pin "27") (pinfunction "VSS_4_27") (pintype "power_in"))
      (node (ref "U2") (pin "49") (pinfunction "VSS_1_49") (pintype "power_in"))
      (node (ref "U2") (pin "74") (pinfunction "VSS_2_74") (pintype "power_in"))
      (node (ref "U2") (pin "99") (pinfunction "VSS_3_99") (pintype "power_in"))
    )
    (net (code "104") (name "Net-(D1-K)") (class "Default")
      (node (ref "D1") (pin "2") (pinfunction "K_2") (pintype "passive"))
      (node (ref "R3") (pin "1") (pintype "passive"))
    )
    (net (code "105") (name "Net-(D3-A)") (class "Default")
      (node (ref "D3") (pin "1") (pinfunction "A_1") (pintype "passive"))
      (node (ref "R1") (pin "2") (pintype "passive"))
    )
    (net (code "106") (name "Net-(D4-A)") (class "Default")
      (node (ref "D4") (pin "1") (pinfunction "A_1") (pintype "passive"))
      (node (ref "R4") (pin "2") (pintype "passive"))
    )
    (net (code "107") (name "Net-(P14-CC-PadA5)") (class "Default")
      (node (ref "P14") (pin "A5") (pinfunction "CC_A5") (pintype "bidirectional"))
      (node (ref "R25") (pin "1") (pinfunction "1_1") (pintype "passive"))
    )
    (net (code "108") (name "Net-(P14-CC-PadB5)") (class "Default")
      (node (ref "P14") (pin "B5") (pinfunction "CC_B5") (pintype "bidirectional"))
      (node (ref "R26") (pin "1") (pinfunction "1_1") (pintype "passive"))
    )
    (net (code "109") (name "Net-(R5-Pad2)") (class "Default")
      (node (ref "R5") (pin "2") (pintype "passive"))
      (node (ref "S2") (pin "2") (pinfunction "2_2") (pintype "passive"))
    )
    (net (code "110") (name "Net-(R20-Pad2)") (class "Default")
      (node (ref "R20") (pin "2") (pinfunction "2_2") (pintype "passive"))
      (node (ref "S4") (pin "2") (pinfunction "2_2") (pintype "passive"))
    )
    (net (code "111") (name "Net-(S1-COMMON)") (class "Default")
      (node (ref "F1") (pin "2") (pinfunction "2_2") (pintype "passive"))
      (node (ref "S1") (pin "1") (pinfunction "COMMON_1") (pintype "passive"))
    )
    (net (code "112") (name "Net-(S1-NC)") (class "Default")
      (node (ref "C1") (pin "1") (pinfunction "1_1") (pintype "passive"))
      (node (ref "S1") (pin "2") (pinfunction "NC_2") (pintype "passive"))
      (node (ref "U1") (pin "3") (pinfunction "Vin_3") (pintype "passive"))
    )
    (net (code "113") (name "unconnected-(P14-RFU1-PadA8)") (class "Default")
      (node (ref "P14") (pin "A8") (pinfunction "RFU1_A8") (pintype "bidirectional+no_connect"))
    )
    (net (code "114") (name "unconnected-(P14-RFU1-PadB8)") (class "Default")
      (node (ref "P14") (pin "B8") (pinfunction "RFU1_B8") (pintype "bidirectional+no_connect"))
    )
    (net (code "115") (name "unconnected-(S1-NO-Pad3)") (class "Default")
      (node (ref "S1") (pin "3") (pinfunction "NO_3") (pintype "passive"))
    )
  )
)
